# Nakuja_Ignition.net
KiCad netlist of a schematic drawn in EasyEDA
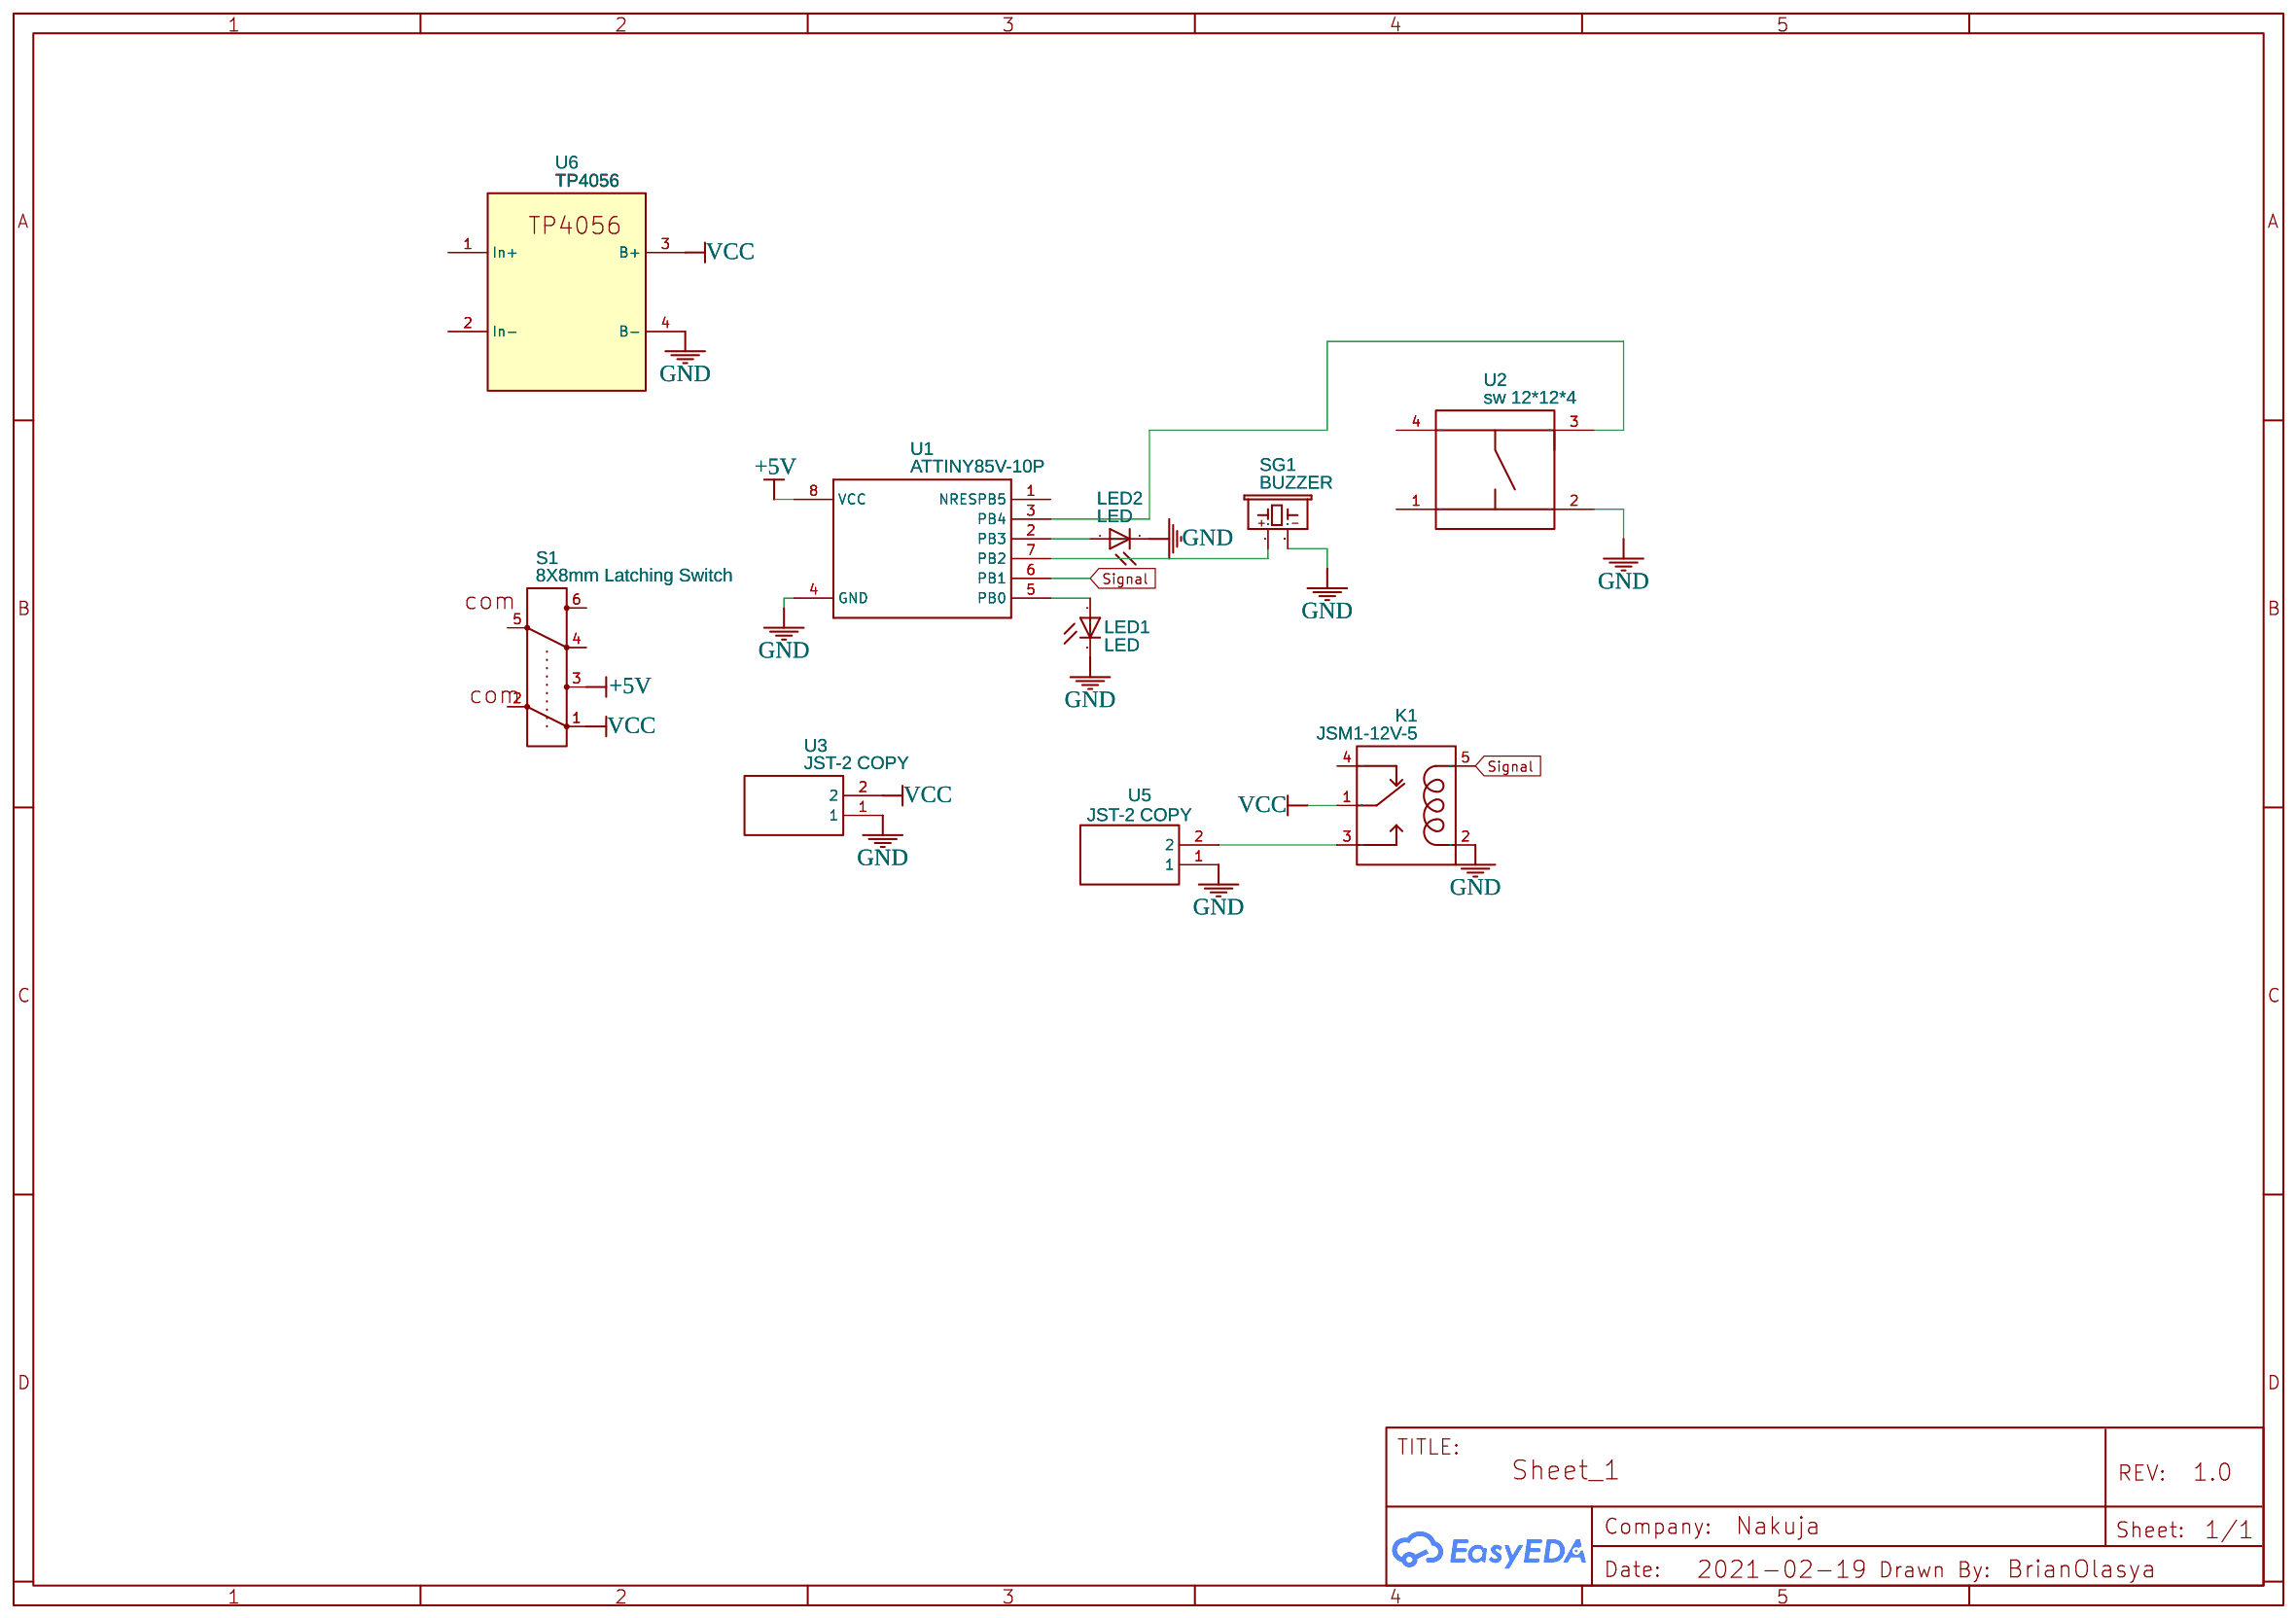
[diagram p0: schematic sheet]

(export (version "E")
  (design (tool "Eeschema 10.0.6"))
  (components
    (comp (ref "K1")
      (value "JSM1-12V-5")
      (fields (field (name "BOM_Supplier Part") "C148306"))
      (libsource (lib "") (part "JSM1-12V-5"))
    )
    (comp (ref "LED1") (value "LED") (libsource (lib "") (part "LED")))
    (comp (ref "LED2") (value "LED") (libsource (lib "") (part "LED_1")))
    (comp (ref "S1")
      (value "8X8mm Latching Switch")
      (fields (field (name "BOM_Manufacturer Part") "New SchematicLib"))
      (libsource (lib "") (part "8X8mm Latching Switch"))
    )
    (comp (ref "SG1") (value "BUZZER") (libsource (lib "") (part "BUZZER")))
    (comp (ref "U1") (value "ATTINY85V-10P") (libsource (lib "") (part "ATTINY85V-10P")))
    (comp (ref "U2")
      (value "sw 12*12*4")
      (fields (field (name "BOM_Manufacturer Part") "sw"))
      (libsource (lib "") (part "sw 12*12*4"))
    )
    (comp (ref "U3")
      (value "JST-2 COPY")
      (fields (field (name "BOM_Manufacturer Part") "JST-s-PTH"))
      (libsource (lib "") (part "JST-2 COPY"))
    )
    (comp (ref "U5")
      (value "JST-2 COPY")
      (fields (field (name "BOM_Manufacturer Part") "JST-s-PTH"))
      (libsource (lib "") (part "JST-2 COPY"))
    )
    (comp (ref "U6") (value "TP4056") (libsource (lib "") (part "TP4056")))
  )
  (nets
    (net (code "1") (name "+5V") (class "Default")
      (node (ref "S1") (pin "3") (pintype "unspecified"))
      (node (ref "U1") (pin "8") (pinfunction "VCC_8") (pintype "passive"))
    )
    (net (code "2") (name "GND") (class "Default")
      (node (ref "K1") (pin "2") (pinfunction "COIL2_2") (pintype "unspecified"))
      (node (ref "LED1") (pin "K") (pinfunction "C_K") (pintype "unspecified"))
      (node (ref "LED2") (pin "K") (pinfunction "C_K") (pintype "unspecified"))
      (node (ref "SG1") (pin "2") (pinfunction "2_2") (pintype "unspecified"))
      (node (ref "U1") (pin "4") (pinfunction "GND_4") (pintype "passive"))
      (node (ref "U2") (pin "2") (pinfunction "2_2") (pintype "unspecified"))
      (node (ref "U3") (pin "1") (pinfunction "1_1") (pintype "unspecified"))
      (node (ref "U5") (pin "1") (pinfunction "1_1") (pintype "unspecified"))
      (node (ref "U6") (pin "4") (pinfunction "B-_4") (pintype "unspecified"))
    )
    (net (code "3") (name "Net-(K1-NO)") (class "Default")
      (node (ref "K1") (pin "3") (pinfunction "NO_3") (pintype "unspecified"))
      (node (ref "U5") (pin "2") (pinfunction "2_2") (pintype "unspecified"))
    )
    (net (code "4") (name "Net-(U1-PB0)") (class "Default")
      (node (ref "LED1") (pin "A") (pinfunction "A_A") (pintype "unspecified"))
      (node (ref "U1") (pin "5") (pinfunction "PB0_5") (pintype "unspecified"))
    )
    (net (code "5") (name "Net-(U1-PB2)") (class "Default")
      (node (ref "SG1") (pin "1") (pinfunction "1_1") (pintype "unspecified"))
      (node (ref "U1") (pin "7") (pinfunction "PB2_7") (pintype "unspecified"))
    )
    (net (code "6") (name "Net-(U1-PB3)") (class "Default")
      (node (ref "LED2") (pin "A") (pinfunction "A_A") (pintype "unspecified"))
      (node (ref "U1") (pin "2") (pinfunction "PB3_2") (pintype "unspecified"))
    )
    (net (code "7") (name "Net-(U1-PB4)") (class "Default")
      (node (ref "U1") (pin "3") (pinfunction "PB4_3") (pintype "unspecified"))
      (node (ref "U2") (pin "3") (pinfunction "3_3") (pintype "unspecified"))
    )
    (net (code "8") (name "Signal") (class "Default")
      (node (ref "K1") (pin "5") (pinfunction "COIL1_5") (pintype "unspecified"))
      (node (ref "U1") (pin "6") (pinfunction "PB1_6") (pintype "unspecified"))
    )
    (net (code "9") (name "VCC") (class "Default")
      (node (ref "K1") (pin "1") (pinfunction "C_1") (pintype "unspecified"))
      (node (ref "S1") (pin "1") (pintype "unspecified"))
      (node (ref "U3") (pin "2") (pinfunction "2_2") (pintype "unspecified"))
      (node (ref "U6") (pin "3") (pinfunction "B+_3") (pintype "unspecified"))
    )
    (net (code "10") (name "unconnected-(K1-NC-Pad4)") (class "Default")
      (node (ref "K1") (pin "4") (pinfunction "NC_4") (pintype "unspecified"))
    )
    (net (code "11") (name "unconnected-(S1-Pad2)") (class "Default")
      (node (ref "S1") (pin "2") (pintype "unspecified"))
    )
    (net (code "12") (name "unconnected-(S1-Pad4)") (class "Default")
      (node (ref "S1") (pin "4") (pintype "unspecified"))
    )
    (net (code "13") (name "unconnected-(S1-Pad5)") (class "Default")
      (node (ref "S1") (pin "5") (pintype "unspecified"))
    )
    (net (code "14") (name "unconnected-(S1-Pad6)") (class "Default")
      (node (ref "S1") (pin "6") (pintype "unspecified"))
    )
    (net (code "15") (name "unconnected-(U1-NRESPB5-Pad1)") (class "Default")
      (node (ref "U1") (pin "1") (pinfunction "NRESPB5_1") (pintype "unspecified"))
    )
    (net (code "16") (name "unconnected-(U2-Pad1)") (class "Default")
      (node (ref "U2") (pin "1") (pinfunction "1_1") (pintype "unspecified"))
    )
    (net (code "17") (name "unconnected-(U2-Pad4)") (class "Default")
      (node (ref "U2") (pin "4") (pinfunction "4_4") (pintype "unspecified"))
    )
    (net (code "18") (name "unconnected-(U6-In+-Pad1)") (class "Default")
      (node (ref "U6") (pin "1") (pinfunction "In+_1") (pintype "unspecified"))
    )
    (net (code "19") (name "unconnected-(U6-In--Pad2)") (class "Default")
      (node (ref "U6") (pin "2") (pinfunction "In-_2") (pintype "unspecified"))
    )
  )
)
